# protoboard.net
KiCad netlist of a schematic drawn in EAGLE
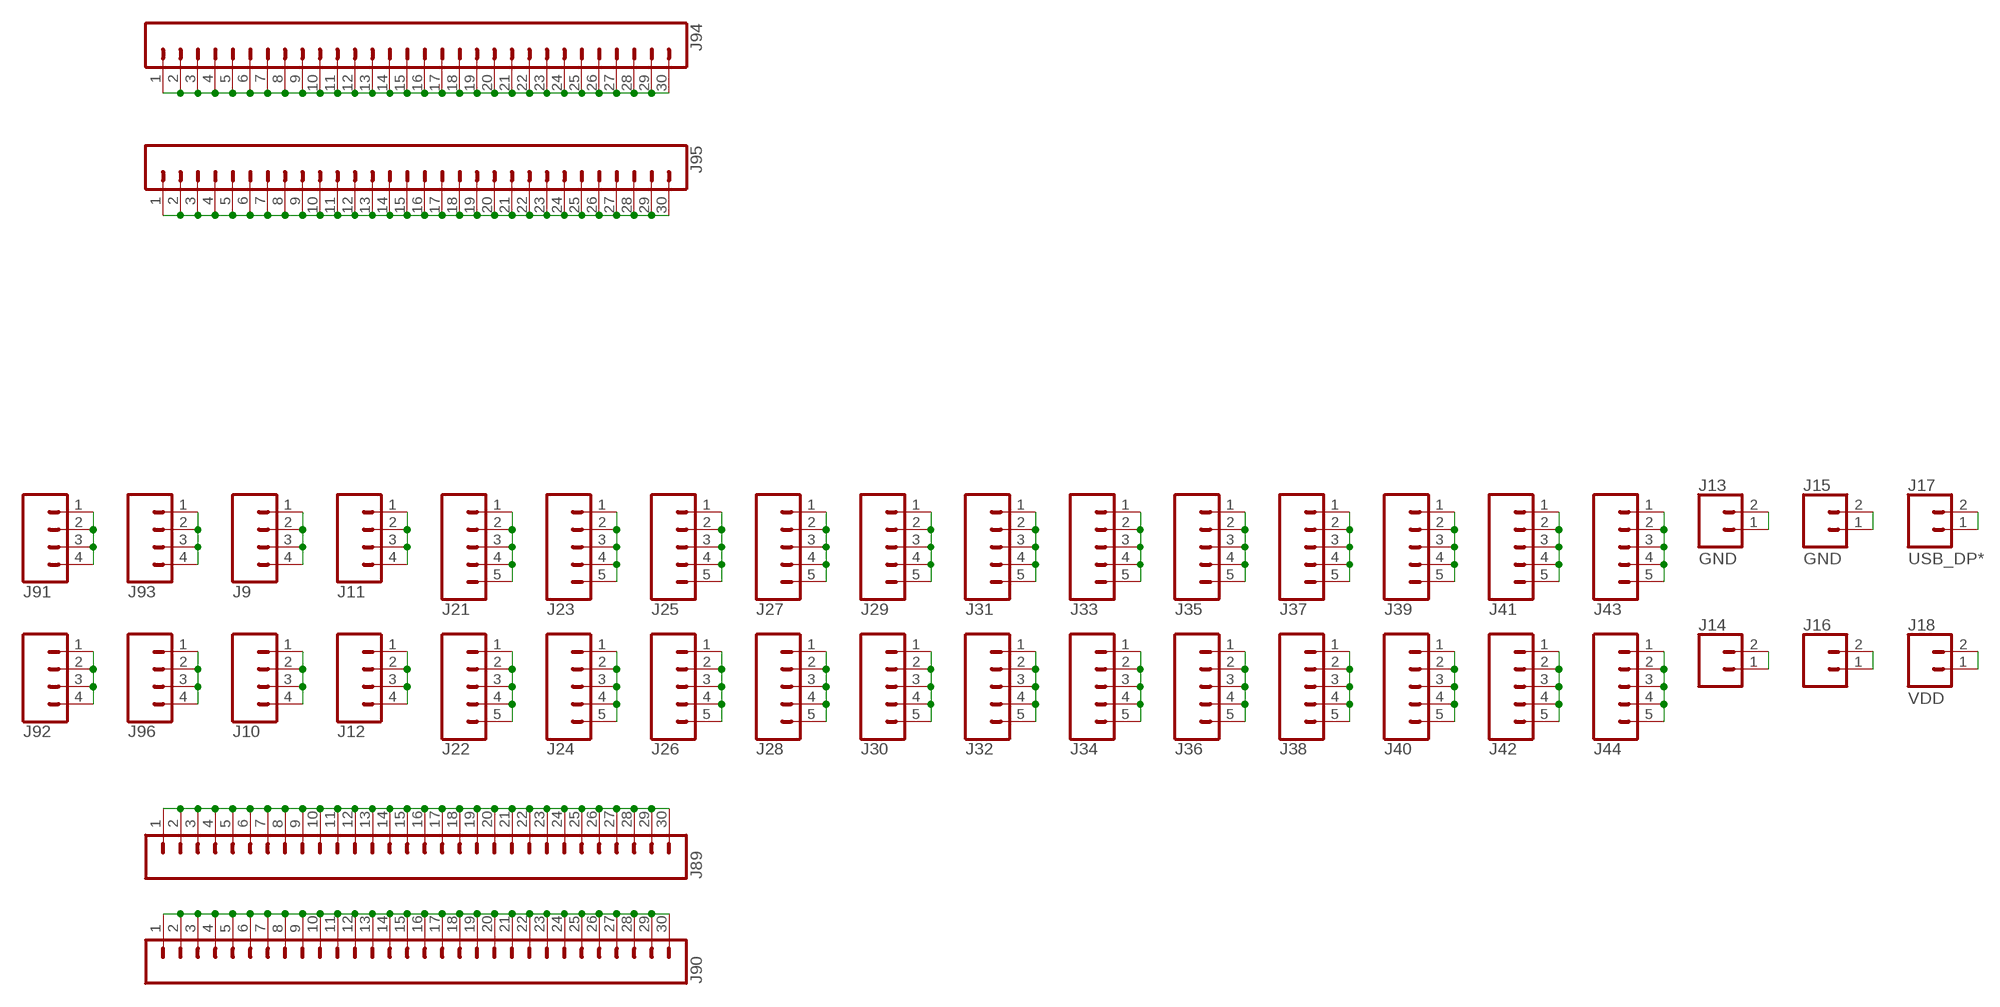
[diagram p0: schematic, sheet 1, part 1 of 2]
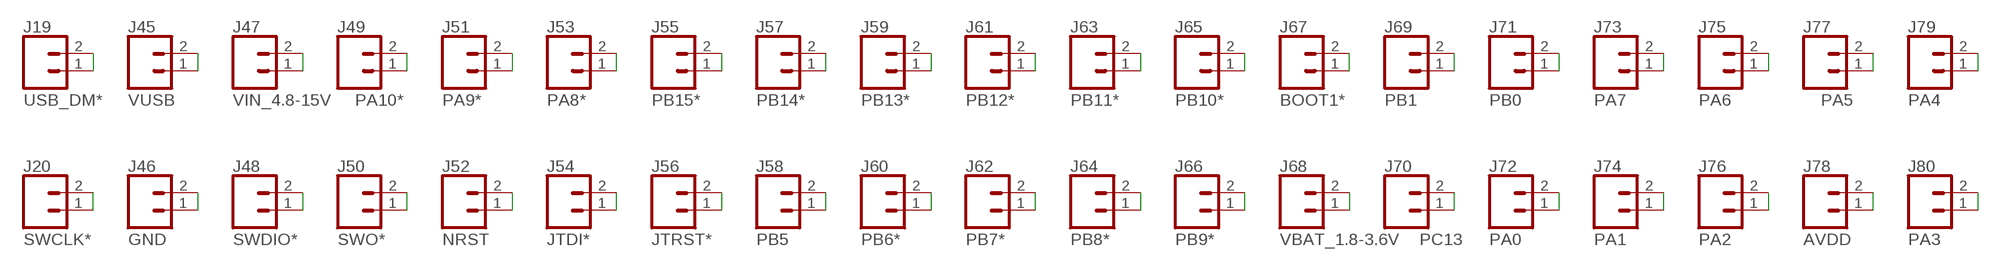
[diagram p1: schematic, sheet 1, part 2 of 2]
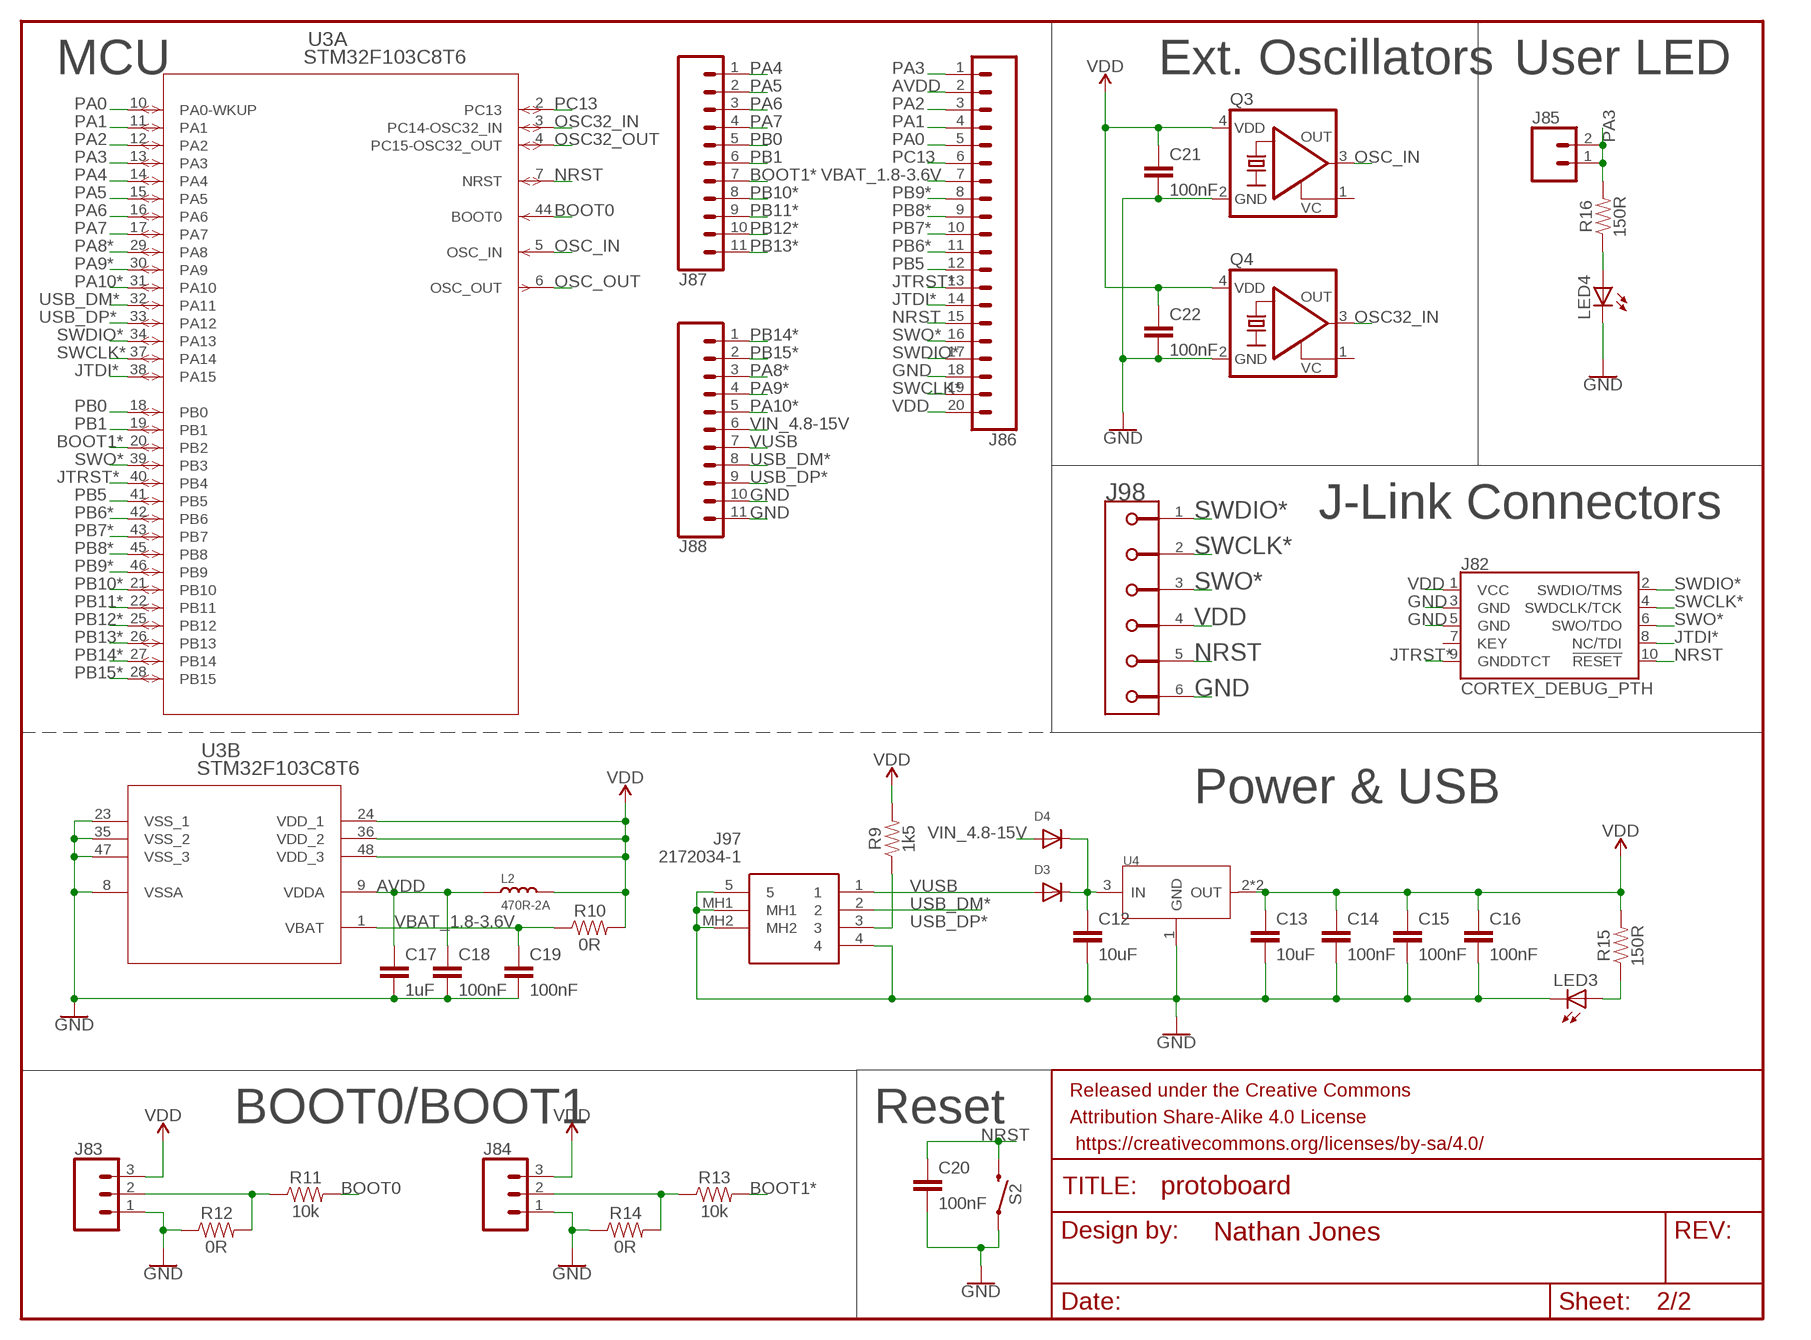
[diagram p2: schematic, sheet 2]

(export (version "E")
  (design (tool "Eeschema 10.0.6"))
  (components
    (comp (ref "C12")
      (value "10uF")
      (footprint "eagle-import:0402-TIGHT")
      (fields (field (name "LCSC_PART") "C15525"))
      (libsource (lib "eagle-import") (part "0.1UF-0402T-16V-10%"))
    )
    (comp (ref "C13")
      (value "10uF")
      (footprint "eagle-import:0402-TIGHT")
      (fields (field (name "LCSC_PART") "C15525"))
      (libsource (lib "eagle-import") (part "0.1UF-0402T-16V-10%"))
    )
    (comp (ref "C14")
      (value "100nF")
      (footprint "eagle-import:0402-TIGHT")
      (fields (field (name "LCSC_PART") "C1525"))
      (libsource (lib "eagle-import") (part "0.1UF-0402T-16V-10%"))
    )
    (comp (ref "C15")
      (value "100nF")
      (footprint "eagle-import:0402-TIGHT")
      (fields (field (name "LCSC_PART") "C1525"))
      (libsource (lib "eagle-import") (part "0.1UF-0402T-16V-10%"))
    )
    (comp (ref "C16")
      (value "100nF")
      (footprint "eagle-import:0402-TIGHT")
      (fields (field (name "LCSC_PART") "C1525"))
      (libsource (lib "eagle-import") (part "0.1UF-0402T-16V-10%"))
    )
    (comp (ref "C17")
      (value "1uF")
      (footprint "eagle-import:0402-TIGHT")
      (fields (field (name "LCSC_PART") "C52923"))
      (libsource (lib "eagle-import") (part "0.1UF-0402T-16V-10%"))
    )
    (comp (ref "C18")
      (value "100nF")
      (footprint "eagle-import:0402-TIGHT")
      (fields (field (name "LCSC_PART") "C1525"))
      (libsource (lib "eagle-import") (part "0.1UF-0402T-16V-10%"))
    )
    (comp (ref "C19")
      (value "100nF")
      (footprint "eagle-import:0402-TIGHT")
      (fields (field (name "LCSC_PART") "C1525"))
      (libsource (lib "eagle-import") (part "0.1UF-0402T-16V-10%"))
    )
    (comp (ref "C20")
      (value "100nF")
      (footprint "eagle-import:0402-TIGHT")
      (fields (field (name "LCSC_PART") "C1525"))
      (libsource (lib "eagle-import") (part "0.1UF-0402T-16V-10%"))
    )
    (comp (ref "C21")
      (value "100nF")
      (footprint "eagle-import:0402-TIGHT")
      (fields (field (name "LCSC_PART") "C1525"))
      (libsource (lib "eagle-import") (part "0.1UF-0402T-16V-10%"))
    )
    (comp (ref "C22")
      (value "100nF")
      (footprint "eagle-import:0402-TIGHT")
      (fields (field (name "LCSC_PART") "C1525"))
      (libsource (lib "eagle-import") (part "0.1UF-0402T-16V-10%"))
    )
    (comp (ref "D3")
      (value "DIODESOD-123")
      (footprint "eagle-import:SOD-123")
      (fields (field (name "LCSC_PART") "C8598"))
      (libsource (lib "eagle-import") (part "DIODESOD-123"))
    )
    (comp (ref "D4")
      (value "DIODESOD-123")
      (footprint "eagle-import:SOD-123")
      (fields (field (name "LCSC_PART") "C8598"))
      (libsource (lib "eagle-import") (part "DIODESOD-123"))
    )
    (comp (ref "FRAME1")
      (value "FRAME-LETTERNO_PACKAGE")
      (footprint "eagle-import:DUMMY")
      (fields (field (name "DESIGNER") "Nathan Jones") (field (name "DESIGNER_1") "Nathan Jones"))
      (libsource (lib "eagle-import") (part "FRAME-LETTERNO_PACKAGE"))
    )
    (comp (ref "J82")
      (value "CORTEX_DEBUG_PTH")
      (footprint "eagle-import:2X5-PTH-1.27MM")
      (libsource (lib "eagle-import") (part "CORTEX_DEBUG_PTH"))
    )
    (comp (ref "J83")
      (value "CONN_031X03_NO_SILK")
      (footprint "eagle-import:1X03_NO_SILK")
      (libsource (lib "eagle-import") (part "CONN_031X03_NO_SILK"))
    )
    (comp (ref "J84")
      (value "CONN_031X03_NO_SILK")
      (footprint "eagle-import:1X03_NO_SILK")
      (libsource (lib "eagle-import") (part "CONN_031X03_NO_SILK"))
    )
    (comp (ref "J85")
      (value "CONN_021X02_NO_SILK")
      (footprint "eagle-import:1X02_NO_SILK")
      (libsource (lib "eagle-import") (part "CONN_021X02_NO_SILK"))
    )
    (comp (ref "J86")
      (value "CONN_20NOSILK")
      (footprint "eagle-import:1X20_NOSILK")
      (libsource (lib "eagle-import") (part "CONN_20NOSILK"))
    )
    (comp (ref "J87")
      (value "CONN_111X11_NO_SILK")
      (footprint "eagle-import:1X11_NO_SILK")
      (libsource (lib "eagle-import") (part "CONN_111X11_NO_SILK"))
    )
    (comp (ref "J88")
      (value "CONN_111X11_NO_SILK")
      (footprint "eagle-import:1X11_NO_SILK")
      (libsource (lib "eagle-import") (part "CONN_111X11_NO_SILK"))
    )
    (comp (ref "J97")
      (value "2172034-1")
      (footprint "eagle-import:21720341")
      (fields (field (name "MOUSER_PART_NUMBER") "571-2172034-1"))
      (libsource (lib "eagle-import") (part "2172034-1"))
    )
    (comp (ref "J98")
      (value "AVX_6-PIN_009159006061916_33MIL-GAP")
      (footprint "eagle-import:AVX_6-PIN_009159006061916_33MIL-GAP")
      (libsource (lib "eagle-import") (part "AVX_6-PIN_009159006061916_33MIL-GAP"))
    )
    (comp (ref "L2")
      (value "470R-2A")
      (footprint "eagle-import:L0805")
      (fields (field (name "MPN") "WLB2012-471T20") (field (name "LCSC_PART") "C1015"))
      (libsource (lib "eagle-import") (part "SMD-FERRITE-BEAD-470R-2A(0805)'0805'"))
    )
    (comp (ref "LED3")
      (value "LEDCHIPLED_0603")
      (footprint "eagle-import:CHIPLED_0603")
      (fields (field (name "LCSC_PART") "C72041"))
      (libsource (lib "eagle-import") (part "LEDCHIPLED_0603"))
    )
    (comp (ref "LED4")
      (value "LEDCHIPLED_0603")
      (footprint "eagle-import:CHIPLED_0603")
      (fields (field (name "LCSC_PART") "C72038"))
      (libsource (lib "eagle-import") (part "LEDCHIPLED_0603"))
    )
    (comp (ref "Q3")
      (value "KXO-VCXO-CMOS_4")
      (footprint "eagle-import:3.2X2.5_KXO-84-TCXO")
      (fields (field (name "LCSC_PART") "C39097"))
      (libsource (lib "eagle-import") (part "KXO-VCXO-CMOS_4"))
    )
    (comp (ref "Q4")
      (value "KXO-VCXO-CMOS_4")
      (footprint "eagle-import:3.2X2.5_KXO-84-TCXO")
      (fields (field (name "LCSC_PART") "C387415"))
      (libsource (lib "eagle-import") (part "KXO-VCXO-CMOS_4"))
    )
    (comp (ref "R9")
      (value "1k5")
      (footprint "eagle-import:0402")
      (fields (field (name "LCSC_PART") "C25867"))
      (libsource (lib "eagle-import") (part "RESISTOR0402"))
    )
    (comp (ref "R10")
      (value "0R")
      (footprint "eagle-import:0402")
      (fields (field (name "LCSC_PART") "C17168"))
      (libsource (lib "eagle-import") (part "RESISTOR0402"))
    )
    (comp (ref "R11")
      (value "10k")
      (footprint "eagle-import:0402")
      (fields (field (name "LCSC_PART") "C25744"))
      (libsource (lib "eagle-import") (part "RESISTOR0402"))
    )
    (comp (ref "R12")
      (value "0R")
      (footprint "eagle-import:0402")
      (fields (field (name "LCSC_PART") "C17168"))
      (libsource (lib "eagle-import") (part "RESISTOR0402"))
    )
    (comp (ref "R13")
      (value "10k")
      (footprint "eagle-import:0402")
      (fields (field (name "LCSC_PART") "C25744"))
      (libsource (lib "eagle-import") (part "RESISTOR0402"))
    )
    (comp (ref "R14")
      (value "0R")
      (footprint "eagle-import:0402")
      (fields (field (name "LCSC_PART") "C17168"))
      (libsource (lib "eagle-import") (part "RESISTOR0402"))
    )
    (comp (ref "R15")
      (value "150R")
      (footprint "eagle-import:0402")
      (fields (field (name "LCSC_PART") "C25082"))
      (libsource (lib "eagle-import") (part "RESISTOR0402"))
    )
    (comp (ref "R16")
      (value "150R")
      (footprint "eagle-import:0402")
      (fields (field (name "LCSC_PART") "C25082"))
      (libsource (lib "eagle-import") (part "RESISTOR0402"))
    )
    (comp (ref "S2")
      (value "MOMENTARY-SWITCH-SPST-SMD-5.2-REDUNDANT")
      (footprint "eagle-import:TACTILE_SWITCH_SMD_5.2MM")
      (fields (field (name "LCSC_PART") "C318884"))
      (libsource (lib "eagle-import") (part "MOMENTARY-SWITCH-SPST-SMD-5.2-REDUNDANT"))
    )
    (comp (ref "U3")
      (value "STM32F103C8T6")
      (footprint "eagle-import:LQFP48-7X7MM")
      (fields
        (field (name "LCSC_PART") "C94046")
        (field (name "COPYRIGHT") "Copyright (C) 2018 Accelerated Designs. All rights reserved")
      )
      (libsource (lib "eagle-import") (part "STM32F103C8T6"))
    )
    (comp (ref "U4")
      (value "CJT1117-3.3-SOT223")
      (footprint "eagle-import:SOT-223")
      (fields (field (name "MPN") "CJT1117-3.3") (field (name "LCSC_PART") "C6186"))
      (libsource (lib "eagle-import") (part "PMIC-CJT1117-3.3(SOT223)"))
    )
    (comp (ref "J9")
      (value "CONN_041X04_NO_SILK")
      (footprint "eagle-import:1X04_NO_SILK")
      (libsource (lib "eagle-import") (part "CONN_041X04_NO_SILK"))
    )
    (comp (ref "J10")
      (value "CONN_041X04_NO_SILK")
      (footprint "eagle-import:1X04_NO_SILK")
      (libsource (lib "eagle-import") (part "CONN_041X04_NO_SILK"))
    )
    (comp (ref "J11")
      (value "CONN_041X04_NO_SILK")
      (footprint "eagle-import:1X04_NO_SILK")
      (libsource (lib "eagle-import") (part "CONN_041X04_NO_SILK"))
    )
    (comp (ref "J12")
      (value "CONN_041X04_NO_SILK")
      (footprint "eagle-import:1X04_NO_SILK")
      (libsource (lib "eagle-import") (part "CONN_041X04_NO_SILK"))
    )
    (comp (ref "J13")
      (value "CONN_021X02_NO_SILK")
      (footprint "eagle-import:1X02_NO_SILK")
      (libsource (lib "eagle-import") (part "CONN_021X02_NO_SILK"))
    )
    (comp (ref "J14")
      (value "CONN_021X02_NO_SILK")
      (footprint "eagle-import:1X02_NO_SILK")
      (libsource (lib "eagle-import") (part "CONN_021X02_NO_SILK"))
    )
    (comp (ref "J15")
      (value "CONN_021X02_NO_SILK")
      (footprint "eagle-import:1X02_NO_SILK")
      (libsource (lib "eagle-import") (part "CONN_021X02_NO_SILK"))
    )
    (comp (ref "J16")
      (value "CONN_021X02_NO_SILK")
      (footprint "eagle-import:1X02_NO_SILK")
      (libsource (lib "eagle-import") (part "CONN_021X02_NO_SILK"))
    )
    (comp (ref "J17")
      (value "CONN_021X02_NO_SILK")
      (footprint "eagle-import:1X02_NO_SILK")
      (libsource (lib "eagle-import") (part "CONN_021X02_NO_SILK"))
    )
    (comp (ref "J18")
      (value "CONN_021X02_NO_SILK")
      (footprint "eagle-import:1X02_NO_SILK")
      (libsource (lib "eagle-import") (part "CONN_021X02_NO_SILK"))
    )
    (comp (ref "J19")
      (value "CONN_021X02_NO_SILK")
      (footprint "eagle-import:1X02_NO_SILK")
      (libsource (lib "eagle-import") (part "CONN_021X02_NO_SILK"))
    )
    (comp (ref "J20")
      (value "CONN_021X02_NO_SILK")
      (footprint "eagle-import:1X02_NO_SILK")
      (libsource (lib "eagle-import") (part "CONN_021X02_NO_SILK"))
    )
    (comp (ref "J21")
      (value "CONN_05NO_SILK")
      (footprint "eagle-import:1X05_NO_SILK")
      (libsource (lib "eagle-import") (part "CONN_05NO_SILK"))
    )
    (comp (ref "J22")
      (value "CONN_05NO_SILK")
      (footprint "eagle-import:1X05_NO_SILK")
      (libsource (lib "eagle-import") (part "CONN_05NO_SILK"))
    )
    (comp (ref "J23")
      (value "CONN_05NO_SILK")
      (footprint "eagle-import:1X05_NO_SILK")
      (libsource (lib "eagle-import") (part "CONN_05NO_SILK"))
    )
    (comp (ref "J24")
      (value "CONN_05NO_SILK")
      (footprint "eagle-import:1X05_NO_SILK")
      (libsource (lib "eagle-import") (part "CONN_05NO_SILK"))
    )
    (comp (ref "J25")
      (value "CONN_05NO_SILK")
      (footprint "eagle-import:1X05_NO_SILK")
      (libsource (lib "eagle-import") (part "CONN_05NO_SILK"))
    )
    (comp (ref "J26")
      (value "CONN_05NO_SILK")
      (footprint "eagle-import:1X05_NO_SILK")
      (libsource (lib "eagle-import") (part "CONN_05NO_SILK"))
    )
    (comp (ref "J27")
      (value "CONN_05NO_SILK")
      (footprint "eagle-import:1X05_NO_SILK")
      (libsource (lib "eagle-import") (part "CONN_05NO_SILK"))
    )
    (comp (ref "J28")
      (value "CONN_05NO_SILK")
      (footprint "eagle-import:1X05_NO_SILK")
      (libsource (lib "eagle-import") (part "CONN_05NO_SILK"))
    )
    (comp (ref "J29")
      (value "CONN_05NO_SILK")
      (footprint "eagle-import:1X05_NO_SILK")
      (libsource (lib "eagle-import") (part "CONN_05NO_SILK"))
    )
    (comp (ref "J30")
      (value "CONN_05NO_SILK")
      (footprint "eagle-import:1X05_NO_SILK")
      (libsource (lib "eagle-import") (part "CONN_05NO_SILK"))
    )
    (comp (ref "J31")
      (value "CONN_05NO_SILK")
      (footprint "eagle-import:1X05_NO_SILK")
      (libsource (lib "eagle-import") (part "CONN_05NO_SILK"))
    )
    (comp (ref "J32")
      (value "CONN_05NO_SILK")
      (footprint "eagle-import:1X05_NO_SILK")
      (libsource (lib "eagle-import") (part "CONN_05NO_SILK"))
    )
    (comp (ref "J33")
      (value "CONN_05NO_SILK")
      (footprint "eagle-import:1X05_NO_SILK")
      (libsource (lib "eagle-import") (part "CONN_05NO_SILK"))
    )
    (comp (ref "J34")
      (value "CONN_05NO_SILK")
      (footprint "eagle-import:1X05_NO_SILK")
      (libsource (lib "eagle-import") (part "CONN_05NO_SILK"))
    )
    (comp (ref "J35")
      (value "CONN_05NO_SILK")
      (footprint "eagle-import:1X05_NO_SILK")
      (libsource (lib "eagle-import") (part "CONN_05NO_SILK"))
    )
    (comp (ref "J36")
      (value "CONN_05NO_SILK")
      (footprint "eagle-import:1X05_NO_SILK")
      (libsource (lib "eagle-import") (part "CONN_05NO_SILK"))
    )
    (comp (ref "J37")
      (value "CONN_05NO_SILK")
      (footprint "eagle-import:1X05_NO_SILK")
      (libsource (lib "eagle-import") (part "CONN_05NO_SILK"))
    )
    (comp (ref "J38")
      (value "CONN_05NO_SILK")
      (footprint "eagle-import:1X05_NO_SILK")
      (libsource (lib "eagle-import") (part "CONN_05NO_SILK"))
    )
    (comp (ref "J39")
      (value "CONN_05NO_SILK")
      (footprint "eagle-import:1X05_NO_SILK")
      (libsource (lib "eagle-import") (part "CONN_05NO_SILK"))
    )
    (comp (ref "J40")
      (value "CONN_05NO_SILK")
      (footprint "eagle-import:1X05_NO_SILK")
      (libsource (lib "eagle-import") (part "CONN_05NO_SILK"))
    )
    (comp (ref "J41")
      (value "CONN_05NO_SILK")
      (footprint "eagle-import:1X05_NO_SILK")
      (libsource (lib "eagle-import") (part "CONN_05NO_SILK"))
    )
    (comp (ref "J42")
      (value "CONN_05NO_SILK")
      (footprint "eagle-import:1X05_NO_SILK")
      (libsource (lib "eagle-import") (part "CONN_05NO_SILK"))
    )
    (comp (ref "J43")
      (value "CONN_05NO_SILK")
      (footprint "eagle-import:1X05_NO_SILK")
      (libsource (lib "eagle-import") (part "CONN_05NO_SILK"))
    )
    (comp (ref "J44")
      (value "CONN_05NO_SILK")
      (footprint "eagle-import:1X05_NO_SILK")
      (libsource (lib "eagle-import") (part "CONN_05NO_SILK"))
    )
    (comp (ref "J45")
      (value "CONN_021X02_NO_SILK")
      (footprint "eagle-import:1X02_NO_SILK")
      (libsource (lib "eagle-import") (part "CONN_021X02_NO_SILK"))
    )
    (comp (ref "J46")
      (value "CONN_021X02_NO_SILK")
      (footprint "eagle-import:1X02_NO_SILK")
      (libsource (lib "eagle-import") (part "CONN_021X02_NO_SILK"))
    )
    (comp (ref "J47")
      (value "CONN_021X02_NO_SILK")
      (footprint "eagle-import:1X02_NO_SILK")
      (libsource (lib "eagle-import") (part "CONN_021X02_NO_SILK"))
    )
    (comp (ref "J48")
      (value "CONN_021X02_NO_SILK")
      (footprint "eagle-import:1X02_NO_SILK")
      (libsource (lib "eagle-import") (part "CONN_021X02_NO_SILK"))
    )
    (comp (ref "J49")
      (value "CONN_021X02_NO_SILK")
      (footprint "eagle-import:1X02_NO_SILK")
      (libsource (lib "eagle-import") (part "CONN_021X02_NO_SILK"))
    )
    (comp (ref "J50")
      (value "CONN_021X02_NO_SILK")
      (footprint "eagle-import:1X02_NO_SILK")
      (libsource (lib "eagle-import") (part "CONN_021X02_NO_SILK"))
    )
    (comp (ref "J51")
      (value "CONN_021X02_NO_SILK")
      (footprint "eagle-import:1X02_NO_SILK")
      (libsource (lib "eagle-import") (part "CONN_021X02_NO_SILK"))
    )
    (comp (ref "J52")
      (value "CONN_021X02_NO_SILK")
      (footprint "eagle-import:1X02_NO_SILK")
      (libsource (lib "eagle-import") (part "CONN_021X02_NO_SILK"))
    )
    (comp (ref "J53")
      (value "CONN_021X02_NO_SILK")
      (footprint "eagle-import:1X02_NO_SILK")
      (libsource (lib "eagle-import") (part "CONN_021X02_NO_SILK"))
    )
    (comp (ref "J54")
      (value "CONN_021X02_NO_SILK")
      (footprint "eagle-import:1X02_NO_SILK")
      (libsource (lib "eagle-import") (part "CONN_021X02_NO_SILK"))
    )
    (comp (ref "J55")
      (value "CONN_021X02_NO_SILK")
      (footprint "eagle-import:1X02_NO_SILK")
      (libsource (lib "eagle-import") (part "CONN_021X02_NO_SILK"))
    )
    (comp (ref "J56")
      (value "CONN_021X02_NO_SILK")
      (footprint "eagle-import:1X02_NO_SILK")
      (libsource (lib "eagle-import") (part "CONN_021X02_NO_SILK"))
    )
    (comp (ref "J57")
      (value "CONN_021X02_NO_SILK")
      (footprint "eagle-import:1X02_NO_SILK")
      (libsource (lib "eagle-import") (part "CONN_021X02_NO_SILK"))
    )
    (comp (ref "J58")
      (value "CONN_021X02_NO_SILK")
      (footprint "eagle-import:1X02_NO_SILK")
      (libsource (lib "eagle-import") (part "CONN_021X02_NO_SILK"))
    )
    (comp (ref "J59")
      (value "CONN_021X02_NO_SILK")
      (footprint "eagle-import:1X02_NO_SILK")
      (libsource (lib "eagle-import") (part "CONN_021X02_NO_SILK"))
    )
    (comp (ref "J60")
      (value "CONN_021X02_NO_SILK")
      (footprint "eagle-import:1X02_NO_SILK")
      (libsource (lib "eagle-import") (part "CONN_021X02_NO_SILK"))
    )
    (comp (ref "J61")
      (value "CONN_021X02_NO_SILK")
      (footprint "eagle-import:1X02_NO_SILK")
      (libsource (lib "eagle-import") (part "CONN_021X02_NO_SILK"))
    )
    (comp (ref "J62")
      (value "CONN_021X02_NO_SILK")
      (footprint "eagle-import:1X02_NO_SILK")
      (libsource (lib "eagle-import") (part "CONN_021X02_NO_SILK"))
    )
    (comp (ref "J63")
      (value "CONN_021X02_NO_SILK")
      (footprint "eagle-import:1X02_NO_SILK")
      (libsource (lib "eagle-import") (part "CONN_021X02_NO_SILK"))
    )
    (comp (ref "J64")
      (value "CONN_021X02_NO_SILK")
      (footprint "eagle-import:1X02_NO_SILK")
      (libsource (lib "eagle-import") (part "CONN_021X02_NO_SILK"))
    )
    (comp (ref "J65")
      (value "CONN_021X02_NO_SILK")
      (footprint "eagle-import:1X02_NO_SILK")
      (libsource (lib "eagle-import") (part "CONN_021X02_NO_SILK"))
    )
    (comp (ref "J66")
      (value "CONN_021X02_NO_SILK")
      (footprint "eagle-import:1X02_NO_SILK")
      (libsource (lib "eagle-import") (part "CONN_021X02_NO_SILK"))
    )
    (comp (ref "J67")
      (value "CONN_021X02_NO_SILK")
      (footprint "eagle-import:1X02_NO_SILK")
      (libsource (lib "eagle-import") (part "CONN_021X02_NO_SILK"))
    )
    (comp (ref "J68")
      (value "CONN_021X02_NO_SILK")
      (footprint "eagle-import:1X02_NO_SILK")
      (libsource (lib "eagle-import") (part "CONN_021X02_NO_SILK"))
    )
    (comp (ref "J69")
      (value "CONN_021X02_NO_SILK")
      (footprint "eagle-import:1X02_NO_SILK")
      (libsource (lib "eagle-import") (part "CONN_021X02_NO_SILK"))
    )
    (comp (ref "J70")
      (value "CONN_021X02_NO_SILK")
      (footprint "eagle-import:1X02_NO_SILK")
      (libsource (lib "eagle-import") (part "CONN_021X02_NO_SILK"))
    )
    (comp (ref "J71")
      (value "CONN_021X02_NO_SILK")
      (footprint "eagle-import:1X02_NO_SILK")
      (libsource (lib "eagle-import") (part "CONN_021X02_NO_SILK"))
    )
    (comp (ref "J72")
      (value "CONN_021X02_NO_SILK")
      (footprint "eagle-import:1X02_NO_SILK")
      (libsource (lib "eagle-import") (part "CONN_021X02_NO_SILK"))
    )
    (comp (ref "J73")
      (value "CONN_021X02_NO_SILK")
      (footprint "eagle-import:1X02_NO_SILK")
      (libsource (lib "eagle-import") (part "CONN_021X02_NO_SILK"))
    )
    (comp (ref "J74")
      (value "CONN_021X02_NO_SILK")
      (footprint "eagle-import:1X02_NO_SILK")
      (libsource (lib "eagle-import") (part "CONN_021X02_NO_SILK"))
    )
    (comp (ref "J75")
      (value "CONN_021X02_NO_SILK")
      (footprint "eagle-import:1X02_NO_SILK")
      (libsource (lib "eagle-import") (part "CONN_021X02_NO_SILK"))
    )
    (comp (ref "J76")
      (value "CONN_021X02_NO_SILK")
      (footprint "eagle-import:1X02_NO_SILK")
      (libsource (lib "eagle-import") (part "CONN_021X02_NO_SILK"))
    )
    (comp (ref "J77")
      (value "CONN_021X02_NO_SILK")
      (footprint "eagle-import:1X02_NO_SILK")
      (libsource (lib "eagle-import") (part "CONN_021X02_NO_SILK"))
    )
    (comp (ref "J78")
      (value "CONN_021X02_NO_SILK")
      (footprint "eagle-import:1X02_NO_SILK")
      (libsource (lib "eagle-import") (part "CONN_021X02_NO_SILK"))
    )
    (comp (ref "J79")
      (value "CONN_021X02_NO_SILK")
      (footprint "eagle-import:1X02_NO_SILK")
      (libsource (lib "eagle-import") (part "CONN_021X02_NO_SILK"))
    )
    (comp (ref "J80")
      (value "CONN_021X02_NO_SILK")
      (footprint "eagle-import:1X02_NO_SILK")
      (libsource (lib "eagle-import") (part "CONN_021X02_NO_SILK"))
    )
    (comp (ref "J89")
      (value "CONN_30NO_SILK")
      (footprint "eagle-import:1X30_NO_SILK")
      (libsource (lib "eagle-import") (part "CONN_30NO_SILK"))
    )
    (comp (ref "J90")
      (value "CONN_30NO_SILK")
      (footprint "eagle-import:1X30_NO_SILK")
      (libsource (lib "eagle-import") (part "CONN_30NO_SILK"))
    )
    (comp (ref "J91")
      (value "CONN_041X04_NO_SILK")
      (footprint "eagle-import:1X04_NO_SILK")
      (libsource (lib "eagle-import") (part "CONN_041X04_NO_SILK"))
    )
    (comp (ref "J92")
      (value "CONN_041X04_NO_SILK")
      (footprint "eagle-import:1X04_NO_SILK")
      (libsource (lib "eagle-import") (part "CONN_041X04_NO_SILK"))
    )
    (comp (ref "J93")
      (value "CONN_041X04_NO_SILK")
      (footprint "eagle-import:1X04_NO_SILK")
      (libsource (lib "eagle-import") (part "CONN_041X04_NO_SILK"))
    )
    (comp (ref "J94")
      (value "CONN_30NO_SILK")
      (footprint "eagle-import:1X30_NO_SILK")
      (libsource (lib "eagle-import") (part "CONN_30NO_SILK"))
    )
    (comp (ref "J95")
      (value "CONN_30NO_SILK")
      (footprint "eagle-import:1X30_NO_SILK")
      (libsource (lib "eagle-import") (part "CONN_30NO_SILK"))
    )
    (comp (ref "J96")
      (value "CONN_041X04_NO_SILK")
      (footprint "eagle-import:1X04_NO_SILK")
      (libsource (lib "eagle-import") (part "CONN_041X04_NO_SILK"))
    )
  )
  (nets
    (net (code "1") (name "AVDD") (class "Default")
      (node (ref "C17") (pin "1") (pinfunction "1_1") (pintype "passive"))
      (node (ref "C18") (pin "1") (pinfunction "1_1") (pintype "passive"))
      (node (ref "J78") (pin "1") (pinfunction "1_1") (pintype "passive"))
      (node (ref "J78") (pin "2") (pinfunction "2_2") (pintype "passive"))
      (node (ref "J86") (pin "2") (pinfunction "2_2") (pintype "passive"))
      (node (ref "L2") (pin "1") (pinfunction "1_1") (pintype "passive"))
      (node (ref "U3") (pin "9") (pinfunction "VDDA_9") (pintype "power_in"))
    )
    (net (code "2") (name "BOOT0") (class "Default")
      (node (ref "R11") (pin "2") (pinfunction "2_2") (pintype "passive"))
      (node (ref "U3") (pin "44") (pinfunction "BOOT0_44") (pintype "input"))
    )
    (net (code "3") (name "BOOT1*") (class "Default")
      (node (ref "J67") (pin "1") (pinfunction "1_1") (pintype "passive"))
      (node (ref "J67") (pin "2") (pinfunction "2_2") (pintype "passive"))
      (node (ref "J87") (pin "7") (pinfunction "7_7") (pintype "passive"))
      (node (ref "R13") (pin "2") (pinfunction "2_2") (pintype "passive"))
      (node (ref "U3") (pin "20") (pinfunction "PB2_20") (pintype "bidirectional"))
    )
    (net (code "4") (name "GND") (class "Default")
      (node (ref "C12") (pin "2") (pinfunction "2_2") (pintype "passive"))
      (node (ref "C13") (pin "2") (pinfunction "2_2") (pintype "passive"))
      (node (ref "C14") (pin "2") (pinfunction "2_2") (pintype "passive"))
      (node (ref "C15") (pin "2") (pinfunction "2_2") (pintype "passive"))
      (node (ref "C16") (pin "2") (pinfunction "2_2") (pintype "passive"))
      (node (ref "C17") (pin "2") (pinfunction "2_2") (pintype "passive"))
      (node (ref "C18") (pin "2") (pinfunction "2_2") (pintype "passive"))
      (node (ref "C19") (pin "2") (pinfunction "2_2") (pintype "passive"))
      (node (ref "C20") (pin "2") (pinfunction "2_2") (pintype "passive"))
      (node (ref "C21") (pin "2") (pinfunction "2_2") (pintype "passive"))
      (node (ref "C22") (pin "2") (pinfunction "2_2") (pintype "passive"))
      (node (ref "J13") (pin "1") (pinfunction "1_1") (pintype "passive"))
      (node (ref "J13") (pin "2") (pinfunction "2_2") (pintype "passive"))
      (node (ref "J15") (pin "1") (pinfunction "1_1") (pintype "passive"))
      (node (ref "J15") (pin "2") (pinfunction "2_2") (pintype "passive"))
      (node (ref "J46") (pin "1") (pinfunction "1_1") (pintype "passive"))
      (node (ref "J46") (pin "2") (pinfunction "2_2") (pintype "passive"))
      (node (ref "J82") (pin "3") (pinfunction "GND_3") (pintype "bidirectional"))
      (node (ref "J82") (pin "5") (pinfunction "GND_5") (pintype "bidirectional"))
      (node (ref "J83") (pin "1") (pinfunction "1_1") (pintype "passive"))
      (node (ref "J84") (pin "1") (pinfunction "1_1") (pintype "passive"))
      (node (ref "J86") (pin "18") (pinfunction "18_18") (pintype "passive"))
      (node (ref "J88") (pin "10") (pinfunction "10_10") (pintype "passive"))
      (node (ref "J88") (pin "11") (pinfunction "11_11") (pintype "passive"))
      (node (ref "J97") (pin "4") (pinfunction "4_4") (pintype "bidirectional"))
      (node (ref "J97") (pin "5") (pinfunction "5_5") (pintype "bidirectional"))
      (node (ref "J97") (pin "MH1") (pinfunction "MH1_MH1") (pintype "bidirectional"))
      (node (ref "J97") (pin "MH2") (pinfunction "MH2_MH2") (pintype "bidirectional"))
      (node (ref "J98") (pin "6") (pinfunction "6_6") (pintype "bidirectional"))
      (node (ref "LED3") (pin "C") (pinfunction "C_C") (pintype "passive"))
      (node (ref "LED4") (pin "C") (pinfunction "C_C") (pintype "passive"))
      (node (ref "Q3") (pin "2") (pinfunction "GND_2") (pintype "power_in"))
      (node (ref "Q4") (pin "2") (pinfunction "GND_2") (pintype "power_in"))
      (node (ref "R12") (pin "1") (pinfunction "1_1") (pintype "passive"))
      (node (ref "R14") (pin "1") (pinfunction "1_1") (pintype "passive"))
      (node (ref "S2") (pin "1") (pinfunction "1_1") (pintype "passive"))
      (node (ref "S2") (pin "2") (pinfunction "1_2") (pintype "passive"))
      (node (ref "U3") (pin "23") (pinfunction "VSS_1_23") (pintype "power_in"))
      (node (ref "U3") (pin "35") (pinfunction "VSS_2_35") (pintype "power_in"))
      (node (ref "U3") (pin "47") (pinfunction "VSS_3_47") (pintype "power_in"))
      (node (ref "U3") (pin "8") (pinfunction "VSSA_8") (pintype "power_in"))
      (node (ref "U4") (pin "1") (pinfunction "GND_1") (pintype "bidirectional"))
    )
    (net (code "5") (name "JTDI*") (class "Default")
      (node (ref "J54") (pin "1") (pinfunction "1_1") (pintype "passive"))
      (node (ref "J54") (pin "2") (pinfunction "2_2") (pintype "passive"))
      (node (ref "J82") (pin "8") (pinfunction "NC/TDI_8") (pintype "bidirectional"))
      (node (ref "J86") (pin "14") (pinfunction "14_14") (pintype "passive"))
      (node (ref "U3") (pin "38") (pinfunction "PA15_38") (pintype "bidirectional"))
    )
    (net (code "6") (name "JTRST*") (class "Default")
      (node (ref "J56") (pin "1") (pinfunction "1_1") (pintype "passive"))
      (node (ref "J56") (pin "2") (pinfunction "2_2") (pintype "passive"))
      (node (ref "J82") (pin "9") (pinfunction "GNDDTCT_9") (pintype "bidirectional"))
      (node (ref "J86") (pin "13") (pinfunction "13_13") (pintype "passive"))
      (node (ref "U3") (pin "40") (pinfunction "PB4_40") (pintype "bidirectional"))
    )
    (net (code "7") (name "NRST") (class "Default")
      (node (ref "C20") (pin "1") (pinfunction "1_1") (pintype "passive"))
      (node (ref "J52") (pin "1") (pinfunction "1_1") (pintype "passive"))
      (node (ref "J52") (pin "2") (pinfunction "2_2") (pintype "passive"))
      (node (ref "J82") (pin "10") (pinfunction "~{RESET}_10") (pintype "bidirectional"))
      (node (ref "J86") (pin "15") (pinfunction "15_15") (pintype "passive"))
      (node (ref "J98") (pin "5") (pinfunction "5_5") (pintype "bidirectional"))
      (node (ref "S2") (pin "3") (pinfunction "2_3") (pintype "passive"))
      (node (ref "S2") (pin "4") (pinfunction "2_4") (pintype "passive"))
      (node (ref "U3") (pin "7") (pinfunction "NRST_7") (pintype "bidirectional"))
    )
    (net (code "8") (name "Net-(J9-Pad1)") (class "Default")
      (node (ref "J9") (pin "1") (pinfunction "1_1") (pintype "passive"))
      (node (ref "J9") (pin "2") (pinfunction "2_2") (pintype "passive"))
      (node (ref "J9") (pin "3") (pinfunction "3_3") (pintype "passive"))
      (node (ref "J9") (pin "4") (pinfunction "4_4") (pintype "passive"))
    )
    (net (code "9") (name "Net-(J10-Pad1)") (class "Default")
      (node (ref "J10") (pin "1") (pinfunction "1_1") (pintype "passive"))
      (node (ref "J10") (pin "2") (pinfunction "2_2") (pintype "passive"))
      (node (ref "J10") (pin "3") (pinfunction "3_3") (pintype "passive"))
      (node (ref "J10") (pin "4") (pinfunction "4_4") (pintype "passive"))
    )
    (net (code "10") (name "Net-(J11-Pad1)") (class "Default")
      (node (ref "J11") (pin "1") (pinfunction "1_1") (pintype "passive"))
      (node (ref "J11") (pin "2") (pinfunction "2_2") (pintype "passive"))
      (node (ref "J11") (pin "3") (pinfunction "3_3") (pintype "passive"))
      (node (ref "J11") (pin "4") (pinfunction "4_4") (pintype "passive"))
    )
    (net (code "11") (name "Net-(J12-Pad1)") (class "Default")
      (node (ref "J12") (pin "1") (pinfunction "1_1") (pintype "passive"))
      (node (ref "J12") (pin "2") (pinfunction "2_2") (pintype "passive"))
      (node (ref "J12") (pin "3") (pinfunction "3_3") (pintype "passive"))
      (node (ref "J12") (pin "4") (pinfunction "4_4") (pintype "passive"))
    )
    (net (code "12") (name "Net-(J14-Pad1)") (class "Default")
      (node (ref "J14") (pin "1") (pinfunction "1_1") (pintype "passive"))
      (node (ref "J14") (pin "2") (pinfunction "2_2") (pintype "passive"))
    )
    (net (code "13") (name "Net-(J16-Pad1)") (class "Default")
      (node (ref "J16") (pin "1") (pinfunction "1_1") (pintype "passive"))
      (node (ref "J16") (pin "2") (pinfunction "2_2") (pintype "passive"))
    )
    (net (code "14") (name "Net-(J21-Pad1)") (class "Default")
      (node (ref "J21") (pin "1") (pinfunction "1_1") (pintype "passive"))
      (node (ref "J21") (pin "2") (pinfunction "2_2") (pintype "passive"))
      (node (ref "J21") (pin "3") (pinfunction "3_3") (pintype "passive"))
      (node (ref "J21") (pin "4") (pinfunction "4_4") (pintype "passive"))
      (node (ref "J21") (pin "5") (pinfunction "5_5") (pintype "passive"))
    )
    (net (code "15") (name "Net-(J22-Pad1)") (class "Default")
      (node (ref "J22") (pin "1") (pinfunction "1_1") (pintype "passive"))
      (node (ref "J22") (pin "2") (pinfunction "2_2") (pintype "passive"))
      (node (ref "J22") (pin "3") (pinfunction "3_3") (pintype "passive"))
      (node (ref "J22") (pin "4") (pinfunction "4_4") (pintype "passive"))
      (node (ref "J22") (pin "5") (pinfunction "5_5") (pintype "passive"))
    )
    (net (code "16") (name "Net-(J23-Pad1)") (class "Default")
      (node (ref "J23") (pin "1") (pinfunction "1_1") (pintype "passive"))
      (node (ref "J23") (pin "2") (pinfunction "2_2") (pintype "passive"))
      (node (ref "J23") (pin "3") (pinfunction "3_3") (pintype "passive"))
      (node (ref "J23") (pin "4") (pinfunction "4_4") (pintype "passive"))
      (node (ref "J23") (pin "5") (pinfunction "5_5") (pintype "passive"))
    )
    (net (code "17") (name "Net-(J24-Pad1)") (class "Default")
      (node (ref "J24") (pin "1") (pinfunction "1_1") (pintype "passive"))
      (node (ref "J24") (pin "2") (pinfunction "2_2") (pintype "passive"))
      (node (ref "J24") (pin "3") (pinfunction "3_3") (pintype "passive"))
      (node (ref "J24") (pin "4") (pinfunction "4_4") (pintype "passive"))
      (node (ref "J24") (pin "5") (pinfunction "5_5") (pintype "passive"))
    )
    (net (code "18") (name "Net-(J25-Pad1)") (class "Default")
      (node (ref "J25") (pin "1") (pinfunction "1_1") (pintype "passive"))
      (node (ref "J25") (pin "2") (pinfunction "2_2") (pintype "passive"))
      (node (ref "J25") (pin "3") (pinfunction "3_3") (pintype "passive"))
      (node (ref "J25") (pin "4") (pinfunction "4_4") (pintype "passive"))
      (node (ref "J25") (pin "5") (pinfunction "5_5") (pintype "passive"))
    )
    (net (code "19") (name "Net-(J26-Pad1)") (class "Default")
      (node (ref "J26") (pin "1") (pinfunction "1_1") (pintype "passive"))
      (node (ref "J26") (pin "2") (pinfunction "2_2") (pintype "passive"))
      (node (ref "J26") (pin "3") (pinfunction "3_3") (pintype "passive"))
      (node (ref "J26") (pin "4") (pinfunction "4_4") (pintype "passive"))
      (node (ref "J26") (pin "5") (pinfunction "5_5") (pintype "passive"))
    )
    (net (code "20") (name "Net-(J27-Pad1)") (class "Default")
      (node (ref "J27") (pin "1") (pinfunction "1_1") (pintype "passive"))
      (node (ref "J27") (pin "2") (pinfunction "2_2") (pintype "passive"))
      (node (ref "J27") (pin "3") (pinfunction "3_3") (pintype "passive"))
      (node (ref "J27") (pin "4") (pinfunction "4_4") (pintype "passive"))
      (node (ref "J27") (pin "5") (pinfunction "5_5") (pintype "passive"))
    )
    (net (code "21") (name "Net-(J28-Pad1)") (class "Default")
      (node (ref "J28") (pin "1") (pinfunction "1_1") (pintype "passive"))
      (node (ref "J28") (pin "2") (pinfunction "2_2") (pintype "passive"))
      (node (ref "J28") (pin "3") (pinfunction "3_3") (pintype "passive"))
      (node (ref "J28") (pin "4") (pinfunction "4_4") (pintype "passive"))
      (node (ref "J28") (pin "5") (pinfunction "5_5") (pintype "passive"))
    )
    (net (code "22") (name "Net-(J29-Pad1)") (class "Default")
      (node (ref "J29") (pin "1") (pinfunction "1_1") (pintype "passive"))
      (node (ref "J29") (pin "2") (pinfunction "2_2") (pintype "passive"))
      (node (ref "J29") (pin "3") (pinfunction "3_3") (pintype "passive"))
      (node (ref "J29") (pin "4") (pinfunction "4_4") (pintype "passive"))
      (node (ref "J29") (pin "5") (pinfunction "5_5") (pintype "passive"))
    )
    (net (code "23") (name "Net-(J30-Pad1)") (class "Default")
      (node (ref "J30") (pin "1") (pinfunction "1_1") (pintype "passive"))
      (node (ref "J30") (pin "2") (pinfunction "2_2") (pintype "passive"))
      (node (ref "J30") (pin "3") (pinfunction "3_3") (pintype "passive"))
      (node (ref "J30") (pin "4") (pinfunction "4_4") (pintype "passive"))
      (node (ref "J30") (pin "5") (pinfunction "5_5") (pintype "passive"))
    )
    (net (code "24") (name "Net-(J31-Pad1)") (class "Default")
      (node (ref "J31") (pin "1") (pinfunction "1_1") (pintype "passive"))
      (node (ref "J31") (pin "2") (pinfunction "2_2") (pintype "passive"))
      (node (ref "J31") (pin "3") (pinfunction "3_3") (pintype "passive"))
      (node (ref "J31") (pin "4") (pinfunction "4_4") (pintype "passive"))
      (node (ref "J31") (pin "5") (pinfunction "5_5") (pintype "passive"))
    )
    (net (code "25") (name "Net-(J32-Pad1)") (class "Default")
      (node (ref "J32") (pin "1") (pinfunction "1_1") (pintype "passive"))
      (node (ref "J32") (pin "2") (pinfunction "2_2") (pintype "passive"))
      (node (ref "J32") (pin "3") (pinfunction "3_3") (pintype "passive"))
      (node (ref "J32") (pin "4") (pinfunction "4_4") (pintype "passive"))
      (node (ref "J32") (pin "5") (pinfunction "5_5") (pintype "passive"))
    )
    (net (code "26") (name "Net-(J33-Pad1)") (class "Default")
      (node (ref "J33") (pin "1") (pinfunction "1_1") (pintype "passive"))
      (node (ref "J33") (pin "2") (pinfunction "2_2") (pintype "passive"))
      (node (ref "J33") (pin "3") (pinfunction "3_3") (pintype "passive"))
      (node (ref "J33") (pin "4") (pinfunction "4_4") (pintype "passive"))
      (node (ref "J33") (pin "5") (pinfunction "5_5") (pintype "passive"))
    )
    (net (code "27") (name "Net-(J34-Pad1)") (class "Default")
      (node (ref "J34") (pin "1") (pinfunction "1_1") (pintype "passive"))
      (node (ref "J34") (pin "2") (pinfunction "2_2") (pintype "passive"))
      (node (ref "J34") (pin "3") (pinfunction "3_3") (pintype "passive"))
      (node (ref "J34") (pin "4") (pinfunction "4_4") (pintype "passive"))
      (node (ref "J34") (pin "5") (pinfunction "5_5") (pintype "passive"))
    )
    (net (code "28") (name "Net-(J35-Pad1)") (class "Default")
      (node (ref "J35") (pin "1") (pinfunction "1_1") (pintype "passive"))
      (node (ref "J35") (pin "2") (pinfunction "2_2") (pintype "passive"))
      (node (ref "J35") (pin "3") (pinfunction "3_3") (pintype "passive"))
      (node (ref "J35") (pin "4") (pinfunction "4_4") (pintype "passive"))
      (node (ref "J35") (pin "5") (pinfunction "5_5") (pintype "passive"))
    )
    (net (code "29") (name "Net-(J36-Pad1)") (class "Default")
      (node (ref "J36") (pin "1") (pinfunction "1_1") (pintype "passive"))
      (node (ref "J36") (pin "2") (pinfunction "2_2") (pintype "passive"))
      (node (ref "J36") (pin "3") (pinfunction "3_3") (pintype "passive"))
      (node (ref "J36") (pin "4") (pinfunction "4_4") (pintype "passive"))
      (node (ref "J36") (pin "5") (pinfunction "5_5") (pintype "passive"))
    )
    (net (code "30") (name "Net-(J37-Pad1)") (class "Default")
      (node (ref "J37") (pin "1") (pinfunction "1_1") (pintype "passive"))
      (node (ref "J37") (pin "2") (pinfunction "2_2") (pintype "passive"))
      (node (ref "J37") (pin "3") (pinfunction "3_3") (pintype "passive"))
      (node (ref "J37") (pin "4") (pinfunction "4_4") (pintype "passive"))
      (node (ref "J37") (pin "5") (pinfunction "5_5") (pintype "passive"))
    )
    (net (code "31") (name "Net-(J38-Pad1)") (class "Default")
      (node (ref "J38") (pin "1") (pinfunction "1_1") (pintype "passive"))
      (node (ref "J38") (pin "2") (pinfunction "2_2") (pintype "passive"))
      (node (ref "J38") (pin "3") (pinfunction "3_3") (pintype "passive"))
      (node (ref "J38") (pin "4") (pinfunction "4_4") (pintype "passive"))
      (node (ref "J38") (pin "5") (pinfunction "5_5") (pintype "passive"))
    )
    (net (code "32") (name "Net-(J39-Pad1)") (class "Default")
      (node (ref "J39") (pin "1") (pinfunction "1_1") (pintype "passive"))
      (node (ref "J39") (pin "2") (pinfunction "2_2") (pintype "passive"))
      (node (ref "J39") (pin "3") (pinfunction "3_3") (pintype "passive"))
      (node (ref "J39") (pin "4") (pinfunction "4_4") (pintype "passive"))
      (node (ref "J39") (pin "5") (pinfunction "5_5") (pintype "passive"))
    )
    (net (code "33") (name "Net-(J40-Pad1)") (class "Default")
      (node (ref "J40") (pin "1") (pinfunction "1_1") (pintype "passive"))
      (node (ref "J40") (pin "2") (pinfunction "2_2") (pintype "passive"))
      (node (ref "J40") (pin "3") (pinfunction "3_3") (pintype "passive"))
      (node (ref "J40") (pin "4") (pinfunction "4_4") (pintype "passive"))
      (node (ref "J40") (pin "5") (pinfunction "5_5") (pintype "passive"))
    )
    (net (code "34") (name "Net-(J41-Pad1)") (class "Default")
      (node (ref "J41") (pin "1") (pinfunction "1_1") (pintype "passive"))
      (node (ref "J41") (pin "2") (pinfunction "2_2") (pintype "passive"))
      (node (ref "J41") (pin "3") (pinfunction "3_3") (pintype "passive"))
      (node (ref "J41") (pin "4") (pinfunction "4_4") (pintype "passive"))
      (node (ref "J41") (pin "5") (pinfunction "5_5") (pintype "passive"))
    )
    (net (code "35") (name "Net-(J42-Pad1)") (class "Default")
      (node (ref "J42") (pin "1") (pinfunction "1_1") (pintype "passive"))
      (node (ref "J42") (pin "2") (pinfunction "2_2") (pintype "passive"))
      (node (ref "J42") (pin "3") (pinfunction "3_3") (pintype "passive"))
      (node (ref "J42") (pin "4") (pinfunction "4_4") (pintype "passive"))
      (node (ref "J42") (pin "5") (pinfunction "5_5") (pintype "passive"))
    )
    (net (code "36") (name "Net-(J43-Pad1)") (class "Default")
      (node (ref "J43") (pin "1") (pinfunction "1_1") (pintype "passive"))
      (node (ref "J43") (pin "2") (pinfunction "2_2") (pintype "passive"))
      (node (ref "J43") (pin "3") (pinfunction "3_3") (pintype "passive"))
      (node (ref "J43") (pin "4") (pinfunction "4_4") (pintype "passive"))
      (node (ref "J43") (pin "5") (pinfunction "5_5") (pintype "passive"))
    )
    (net (code "37") (name "Net-(J44-Pad1)") (class "Default")
      (node (ref "J44") (pin "1") (pinfunction "1_1") (pintype "passive"))
      (node (ref "J44") (pin "2") (pinfunction "2_2") (pintype "passive"))
      (node (ref "J44") (pin "3") (pinfunction "3_3") (pintype "passive"))
      (node (ref "J44") (pin "4") (pinfunction "4_4") (pintype "passive"))
      (node (ref "J44") (pin "5") (pinfunction "5_5") (pintype "passive"))
    )
    (net (code "38") (name "Net-(J83-Pad2)") (class "Default")
      (node (ref "J83") (pin "2") (pinfunction "2_2") (pintype "passive"))
      (node (ref "R11") (pin "1") (pinfunction "1_1") (pintype "passive"))
      (node (ref "R12") (pin "2") (pinfunction "2_2") (pintype "passive"))
    )
    (net (code "39") (name "Net-(J84-Pad2)") (class "Default")
      (node (ref "J84") (pin "2") (pinfunction "2_2") (pintype "passive"))
      (node (ref "R13") (pin "1") (pinfunction "1_1") (pintype "passive"))
      (node (ref "R14") (pin "2") (pinfunction "2_2") (pintype "passive"))
    )
    (net (code "40") (name "Net-(J89-Pad1)") (class "Default")
      (node (ref "J89") (pin "1") (pinfunction "1_1") (pintype "passive"))
      (node (ref "J89") (pin "10") (pinfunction "10_10") (pintype "passive"))
      (node (ref "J89") (pin "11") (pinfunction "11_11") (pintype "passive"))
      (node (ref "J89") (pin "12") (pinfunction "12_12") (pintype "passive"))
      (node (ref "J89") (pin "13") (pinfunction "13_13") (pintype "passive"))
      (node (ref "J89") (pin "14") (pinfunction "14_14") (pintype "passive"))
      (node (ref "J89") (pin "15") (pinfunction "15_15") (pintype "passive"))
      (node (ref "J89") (pin "16") (pinfunction "16_16") (pintype "passive"))
      (node (ref "J89") (pin "17") (pinfunction "17_17") (pintype "passive"))
      (node (ref "J89") (pin "18") (pinfunction "18_18") (pintype "passive"))
      (node (ref "J89") (pin "19") (pinfunction "19_19") (pintype "passive"))
      (node (ref "J89") (pin "2") (pinfunction "2_2") (pintype "passive"))
      (node (ref "J89") (pin "20") (pinfunction "20_20") (pintype "passive"))
      (node (ref "J89") (pin "21") (pinfunction "21_21") (pintype "passive"))
      (node (ref "J89") (pin "22") (pinfunction "22_22") (pintype "passive"))
      (node (ref "J89") (pin "23") (pinfunction "23_23") (pintype "passive"))
      (node (ref "J89") (pin "24") (pinfunction "24_24") (pintype "passive"))
      (node (ref "J89") (pin "25") (pinfunction "25_25") (pintype "passive"))
      (node (ref "J89") (pin "26") (pinfunction "26_26") (pintype "passive"))
      (node (ref "J89") (pin "27") (pinfunction "27_27") (pintype "passive"))
      (node (ref "J89") (pin "28") (pinfunction "28_28") (pintype "passive"))
      (node (ref "J89") (pin "29") (pinfunction "29_29") (pintype "passive"))
      (node (ref "J89") (pin "3") (pinfunction "3_3") (pintype "passive"))
      (node (ref "J89") (pin "30") (pinfunction "30_30") (pintype "passive"))
      (node (ref "J89") (pin "4") (pinfunction "4_4") (pintype "passive"))
      (node (ref "J89") (pin "5") (pinfunction "5_5") (pintype "passive"))
      (node (ref "J89") (pin "6") (pinfunction "6_6") (pintype "passive"))
      (node (ref "J89") (pin "7") (pinfunction "7_7") (pintype "passive"))
      (node (ref "J89") (pin "8") (pinfunction "8_8") (pintype "passive"))
      (node (ref "J89") (pin "9") (pinfunction "9_9") (pintype "passive"))
    )
    (net (code "41") (name "Net-(J90-Pad1)") (class "Default")
      (node (ref "J90") (pin "1") (pinfunction "1_1") (pintype "passive"))
      (node (ref "J90") (pin "10") (pinfunction "10_10") (pintype "passive"))
      (node (ref "J90") (pin "11") (pinfunction "11_11") (pintype "passive"))
      (node (ref "J90") (pin "12") (pinfunction "12_12") (pintype "passive"))
      (node (ref "J90") (pin "13") (pinfunction "13_13") (pintype "passive"))
      (node (ref "J90") (pin "14") (pinfunction "14_14") (pintype "passive"))
      (node (ref "J90") (pin "15") (pinfunction "15_15") (pintype "passive"))
      (node (ref "J90") (pin "16") (pinfunction "16_16") (pintype "passive"))
      (node (ref "J90") (pin "17") (pinfunction "17_17") (pintype "passive"))
      (node (ref "J90") (pin "18") (pinfunction "18_18") (pintype "passive"))
      (node (ref "J90") (pin "19") (pinfunction "19_19") (pintype "passive"))
      (node (ref "J90") (pin "2") (pinfunction "2_2") (pintype "passive"))
      (node (ref "J90") (pin "20") (pinfunction "20_20") (pintype "passive"))
      (node (ref "J90") (pin "21") (pinfunction "21_21") (pintype "passive"))
      (node (ref "J90") (pin "22") (pinfunction "22_22") (pintype "passive"))
      (node (ref "J90") (pin "23") (pinfunction "23_23") (pintype "passive"))
      (node (ref "J90") (pin "24") (pinfunction "24_24") (pintype "passive"))
      (node (ref "J90") (pin "25") (pinfunction "25_25") (pintype "passive"))
      (node (ref "J90") (pin "26") (pinfunction "26_26") (pintype "passive"))
      (node (ref "J90") (pin "27") (pinfunction "27_27") (pintype "passive"))
      (node (ref "J90") (pin "28") (pinfunction "28_28") (pintype "passive"))
      (node (ref "J90") (pin "29") (pinfunction "29_29") (pintype "passive"))
      (node (ref "J90") (pin "3") (pinfunction "3_3") (pintype "passive"))
      (node (ref "J90") (pin "30") (pinfunction "30_30") (pintype "passive"))
      (node (ref "J90") (pin "4") (pinfunction "4_4") (pintype "passive"))
      (node (ref "J90") (pin "5") (pinfunction "5_5") (pintype "passive"))
      (node (ref "J90") (pin "6") (pinfunction "6_6") (pintype "passive"))
      (node (ref "J90") (pin "7") (pinfunction "7_7") (pintype "passive"))
      (node (ref "J90") (pin "8") (pinfunction "8_8") (pintype "passive"))
      (node (ref "J90") (pin "9") (pinfunction "9_9") (pintype "passive"))
    )
    (net (code "42") (name "Net-(J91-Pad1)") (class "Default")
      (node (ref "J91") (pin "1") (pinfunction "1_1") (pintype "passive"))
      (node (ref "J91") (pin "2") (pinfunction "2_2") (pintype "passive"))
      (node (ref "J91") (pin "3") (pinfunction "3_3") (pintype "passive"))
      (node (ref "J91") (pin "4") (pinfunction "4_4") (pintype "passive"))
    )
    (net (code "43") (name "Net-(J92-Pad1)") (class "Default")
      (node (ref "J92") (pin "1") (pinfunction "1_1") (pintype "passive"))
      (node (ref "J92") (pin "2") (pinfunction "2_2") (pintype "passive"))
      (node (ref "J92") (pin "3") (pinfunction "3_3") (pintype "passive"))
      (node (ref "J92") (pin "4") (pinfunction "4_4") (pintype "passive"))
    )
    (net (code "44") (name "Net-(J93-Pad1)") (class "Default")
      (node (ref "J93") (pin "1") (pinfunction "1_1") (pintype "passive"))
      (node (ref "J93") (pin "2") (pinfunction "2_2") (pintype "passive"))
      (node (ref "J93") (pin "3") (pinfunction "3_3") (pintype "passive"))
      (node (ref "J93") (pin "4") (pinfunction "4_4") (pintype "passive"))
    )
    (net (code "45") (name "Net-(J94-Pad1)") (class "Default")
      (node (ref "J94") (pin "1") (pinfunction "1_1") (pintype "passive"))
      (node (ref "J94") (pin "10") (pinfunction "10_10") (pintype "passive"))
      (node (ref "J94") (pin "11") (pinfunction "11_11") (pintype "passive"))
      (node (ref "J94") (pin "12") (pinfunction "12_12") (pintype "passive"))
      (node (ref "J94") (pin "13") (pinfunction "13_13") (pintype "passive"))
      (node (ref "J94") (pin "14") (pinfunction "14_14") (pintype "passive"))
      (node (ref "J94") (pin "15") (pinfunction "15_15") (pintype "passive"))
      (node (ref "J94") (pin "16") (pinfunction "16_16") (pintype "passive"))
      (node (ref "J94") (pin "17") (pinfunction "17_17") (pintype "passive"))
      (node (ref "J94") (pin "18") (pinfunction "18_18") (pintype "passive"))
      (node (ref "J94") (pin "19") (pinfunction "19_19") (pintype "passive"))
      (node (ref "J94") (pin "2") (pinfunction "2_2") (pintype "passive"))
      (node (ref "J94") (pin "20") (pinfunction "20_20") (pintype "passive"))
      (node (ref "J94") (pin "21") (pinfunction "21_21") (pintype "passive"))
      (node (ref "J94") (pin "22") (pinfunction "22_22") (pintype "passive"))
      (node (ref "J94") (pin "23") (pinfunction "23_23") (pintype "passive"))
      (node (ref "J94") (pin "24") (pinfunction "24_24") (pintype "passive"))
      (node (ref "J94") (pin "25") (pinfunction "25_25") (pintype "passive"))
      (node (ref "J94") (pin "26") (pinfunction "26_26") (pintype "passive"))
      (node (ref "J94") (pin "27") (pinfunction "27_27") (pintype "passive"))
      (node (ref "J94") (pin "28") (pinfunction "28_28") (pintype "passive"))
      (node (ref "J94") (pin "29") (pinfunction "29_29") (pintype "passive"))
      (node (ref "J94") (pin "3") (pinfunction "3_3") (pintype "passive"))
      (node (ref "J94") (pin "30") (pinfunction "30_30") (pintype "passive"))
      (node (ref "J94") (pin "4") (pinfunction "4_4") (pintype "passive"))
      (node (ref "J94") (pin "5") (pinfunction "5_5") (pintype "passive"))
      (node (ref "J94") (pin "6") (pinfunction "6_6") (pintype "passive"))
      (node (ref "J94") (pin "7") (pinfunction "7_7") (pintype "passive"))
      (node (ref "J94") (pin "8") (pinfunction "8_8") (pintype "passive"))
      (node (ref "J94") (pin "9") (pinfunction "9_9") (pintype "passive"))
    )
    (net (code "46") (name "Net-(J95-Pad1)") (class "Default")
      (node (ref "J95") (pin "1") (pinfunction "1_1") (pintype "passive"))
      (node (ref "J95") (pin "10") (pinfunction "10_10") (pintype "passive"))
      (node (ref "J95") (pin "11") (pinfunction "11_11") (pintype "passive"))
      (node (ref "J95") (pin "12") (pinfunction "12_12") (pintype "passive"))
      (node (ref "J95") (pin "13") (pinfunction "13_13") (pintype "passive"))
      (node (ref "J95") (pin "14") (pinfunction "14_14") (pintype "passive"))
      (node (ref "J95") (pin "15") (pinfunction "15_15") (pintype "passive"))
      (node (ref "J95") (pin "16") (pinfunction "16_16") (pintype "passive"))
      (node (ref "J95") (pin "17") (pinfunction "17_17") (pintype "passive"))
      (node (ref "J95") (pin "18") (pinfunction "18_18") (pintype "passive"))
      (node (ref "J95") (pin "19") (pinfunction "19_19") (pintype "passive"))
      (node (ref "J95") (pin "2") (pinfunction "2_2") (pintype "passive"))
      (node (ref "J95") (pin "20") (pinfunction "20_20") (pintype "passive"))
      (node (ref "J95") (pin "21") (pinfunction "21_21") (pintype "passive"))
      (node (ref "J95") (pin "22") (pinfunction "22_22") (pintype "passive"))
      (node (ref "J95") (pin "23") (pinfunction "23_23") (pintype "passive"))
      (node (ref "J95") (pin "24") (pinfunction "24_24") (pintype "passive"))
      (node (ref "J95") (pin "25") (pinfunction "25_25") (pintype "passive"))
      (node (ref "J95") (pin "26") (pinfunction "26_26") (pintype "passive"))
      (node (ref "J95") (pin "27") (pinfunction "27_27") (pintype "passive"))
      (node (ref "J95") (pin "28") (pinfunction "28_28") (pintype "passive"))
      (node (ref "J95") (pin "29") (pinfunction "29_29") (pintype "passive"))
      (node (ref "J95") (pin "3") (pinfunction "3_3") (pintype "passive"))
      (node (ref "J95") (pin "30") (pinfunction "30_30") (pintype "passive"))
      (node (ref "J95") (pin "4") (pinfunction "4_4") (pintype "passive"))
      (node (ref "J95") (pin "5") (pinfunction "5_5") (pintype "passive"))
      (node (ref "J95") (pin "6") (pinfunction "6_6") (pintype "passive"))
      (node (ref "J95") (pin "7") (pinfunction "7_7") (pintype "passive"))
      (node (ref "J95") (pin "8") (pinfunction "8_8") (pintype "passive"))
      (node (ref "J95") (pin "9") (pinfunction "9_9") (pintype "passive"))
    )
    (net (code "47") (name "Net-(J96-Pad1)") (class "Default")
      (node (ref "J96") (pin "1") (pinfunction "1_1") (pintype "passive"))
      (node (ref "J96") (pin "2") (pinfunction "2_2") (pintype "passive"))
      (node (ref "J96") (pin "3") (pinfunction "3_3") (pintype "passive"))
      (node (ref "J96") (pin "4") (pinfunction "4_4") (pintype "passive"))
    )
    (net (code "48") (name "Net-(LED3-PadA)") (class "Default")
      (node (ref "LED3") (pin "A") (pinfunction "A_A") (pintype "passive"))
      (node (ref "R15") (pin "1") (pinfunction "1_1") (pintype "passive"))
    )
    (net (code "49") (name "Net-(LED4-PadA)") (class "Default")
      (node (ref "LED4") (pin "A") (pinfunction "A_A") (pintype "passive"))
      (node (ref "R16") (pin "1") (pinfunction "1_1") (pintype "passive"))
    )
    (net (code "50") (name "Net-(U4-IN)") (class "Default")
      (node (ref "C12") (pin "1") (pinfunction "1_1") (pintype "passive"))
      (node (ref "D3") (pin "C") (pinfunction "C_C") (pintype "passive"))
      (node (ref "D4") (pin "C") (pinfunction "C_C") (pintype "passive"))
      (node (ref "U4") (pin "3") (pinfunction "IN_3") (pintype "bidirectional"))
    )
    (net (code "51") (name "OSC32_IN") (class "Default")
      (node (ref "Q4") (pin "3") (pinfunction "OUT_3") (pintype "output"))
      (node (ref "U3") (pin "3") (pinfunction "PC14-OSC32_IN_3") (pintype "bidirectional"))
    )
    (net (code "52") (name "OSC32_OUT") (class "Default")
      (node (ref "U3") (pin "4") (pinfunction "PC15-OSC32_OUT_4") (pintype "bidirectional"))
    )
    (net (code "53") (name "OSC_IN") (class "Default")
      (node (ref "Q3") (pin "3") (pinfunction "OUT_3") (pintype "output"))
      (node (ref "U3") (pin "5") (pinfunction "OSC_IN_5") (pintype "input"))
    )
    (net (code "54") (name "OSC_OUT") (class "Default")
      (node (ref "U3") (pin "6") (pinfunction "OSC_OUT_6") (pintype "output"))
    )
    (net (code "55") (name "PA0") (class "Default")
      (node (ref "J72") (pin "1") (pinfunction "1_1") (pintype "passive"))
      (node (ref "J72") (pin "2") (pinfunction "2_2") (pintype "passive"))
      (node (ref "J86") (pin "5") (pinfunction "5_5") (pintype "passive"))
      (node (ref "U3") (pin "10") (pinfunction "PA0-WKUP_10") (pintype "bidirectional"))
    )
    (net (code "56") (name "PA1") (class "Default")
      (node (ref "J74") (pin "1") (pinfunction "1_1") (pintype "passive"))
      (node (ref "J74") (pin "2") (pinfunction "2_2") (pintype "passive"))
      (node (ref "J86") (pin "4") (pinfunction "4_4") (pintype "passive"))
      (node (ref "U3") (pin "11") (pinfunction "PA1_11") (pintype "bidirectional"))
    )
    (net (code "57") (name "PA2") (class "Default")
      (node (ref "J76") (pin "1") (pinfunction "1_1") (pintype "passive"))
      (node (ref "J76") (pin "2") (pinfunction "2_2") (pintype "passive"))
      (node (ref "J86") (pin "3") (pinfunction "3_3") (pintype "passive"))
      (node (ref "U3") (pin "12") (pinfunction "PA2_12") (pintype "bidirectional"))
    )
    (net (code "58") (name "PA3") (class "Default")
      (node (ref "J80") (pin "1") (pinfunction "1_1") (pintype "passive"))
      (node (ref "J80") (pin "2") (pinfunction "2_2") (pintype "passive"))
      (node (ref "J85") (pin "1") (pinfunction "1_1") (pintype "passive"))
      (node (ref "J85") (pin "2") (pinfunction "2_2") (pintype "passive"))
      (node (ref "J86") (pin "1") (pinfunction "1_1") (pintype "passive"))
      (node (ref "R16") (pin "2") (pinfunction "2_2") (pintype "passive"))
      (node (ref "U3") (pin "13") (pinfunction "PA3_13") (pintype "bidirectional"))
    )
    (net (code "59") (name "PA4") (class "Default")
      (node (ref "J79") (pin "1") (pinfunction "1_1") (pintype "passive"))
      (node (ref "J79") (pin "2") (pinfunction "2_2") (pintype "passive"))
      (node (ref "J87") (pin "1") (pinfunction "1_1") (pintype "passive"))
      (node (ref "U3") (pin "14") (pinfunction "PA4_14") (pintype "bidirectional"))
    )
    (net (code "60") (name "PA5") (class "Default")
      (node (ref "J77") (pin "1") (pinfunction "1_1") (pintype "passive"))
      (node (ref "J77") (pin "2") (pinfunction "2_2") (pintype "passive"))
      (node (ref "J87") (pin "2") (pinfunction "2_2") (pintype "passive"))
      (node (ref "U3") (pin "15") (pinfunction "PA5_15") (pintype "bidirectional"))
    )
    (net (code "61") (name "PA6") (class "Default")
      (node (ref "J75") (pin "1") (pinfunction "1_1") (pintype "passive"))
      (node (ref "J75") (pin "2") (pinfunction "2_2") (pintype "passive"))
      (node (ref "J87") (pin "3") (pinfunction "3_3") (pintype "passive"))
      (node (ref "U3") (pin "16") (pinfunction "PA6_16") (pintype "bidirectional"))
    )
    (net (code "62") (name "PA7") (class "Default")
      (node (ref "J73") (pin "1") (pinfunction "1_1") (pintype "passive"))
      (node (ref "J73") (pin "2") (pinfunction "2_2") (pintype "passive"))
      (node (ref "J87") (pin "4") (pinfunction "4_4") (pintype "passive"))
      (node (ref "U3") (pin "17") (pinfunction "PA7_17") (pintype "bidirectional"))
    )
    (net (code "63") (name "PA8*") (class "Default")
      (node (ref "J53") (pin "1") (pinfunction "1_1") (pintype "passive"))
      (node (ref "J53") (pin "2") (pinfunction "2_2") (pintype "passive"))
      (node (ref "J88") (pin "3") (pinfunction "3_3") (pintype "passive"))
      (node (ref "U3") (pin "29") (pinfunction "PA8_29") (pintype "bidirectional"))
    )
    (net (code "64") (name "PA9*") (class "Default")
      (node (ref "J51") (pin "1") (pinfunction "1_1") (pintype "passive"))
      (node (ref "J51") (pin "2") (pinfunction "2_2") (pintype "passive"))
      (node (ref "J88") (pin "4") (pinfunction "4_4") (pintype "passive"))
      (node (ref "U3") (pin "30") (pinfunction "PA9_30") (pintype "bidirectional"))
    )
    (net (code "65") (name "PA10*") (class "Default")
      (node (ref "J49") (pin "1") (pinfunction "1_1") (pintype "passive"))
      (node (ref "J49") (pin "2") (pinfunction "2_2") (pintype "passive"))
      (node (ref "J88") (pin "5") (pinfunction "5_5") (pintype "passive"))
      (node (ref "U3") (pin "31") (pinfunction "PA10_31") (pintype "bidirectional"))
    )
    (net (code "66") (name "PB0") (class "Default")
      (node (ref "J71") (pin "1") (pinfunction "1_1") (pintype "passive"))
      (node (ref "J71") (pin "2") (pinfunction "2_2") (pintype "passive"))
      (node (ref "J87") (pin "5") (pinfunction "5_5") (pintype "passive"))
      (node (ref "U3") (pin "18") (pinfunction "PB0_18") (pintype "bidirectional"))
    )
    (net (code "67") (name "PB1") (class "Default")
      (node (ref "J69") (pin "1") (pinfunction "1_1") (pintype "passive"))
      (node (ref "J69") (pin "2") (pinfunction "2_2") (pintype "passive"))
      (node (ref "J87") (pin "6") (pinfunction "6_6") (pintype "passive"))
      (node (ref "U3") (pin "19") (pinfunction "PB1_19") (pintype "bidirectional"))
    )
    (net (code "68") (name "PB5") (class "Default")
      (node (ref "J58") (pin "1") (pinfunction "1_1") (pintype "passive"))
      (node (ref "J58") (pin "2") (pinfunction "2_2") (pintype "passive"))
      (node (ref "J86") (pin "12") (pinfunction "12_12") (pintype "passive"))
      (node (ref "U3") (pin "41") (pinfunction "PB5_41") (pintype "bidirectional"))
    )
    (net (code "69") (name "PB6*") (class "Default")
      (node (ref "J60") (pin "1") (pinfunction "1_1") (pintype "passive"))
      (node (ref "J60") (pin "2") (pinfunction "2_2") (pintype "passive"))
      (node (ref "J86") (pin "11") (pinfunction "11_11") (pintype "passive"))
      (node (ref "U3") (pin "42") (pinfunction "PB6_42") (pintype "bidirectional"))
    )
    (net (code "70") (name "PB7*") (class "Default")
      (node (ref "J62") (pin "1") (pinfunction "1_1") (pintype "passive"))
      (node (ref "J62") (pin "2") (pinfunction "2_2") (pintype "passive"))
      (node (ref "J86") (pin "10") (pinfunction "10_10") (pintype "passive"))
      (node (ref "U3") (pin "43") (pinfunction "PB7_43") (pintype "bidirectional"))
    )
    (net (code "71") (name "PB8*") (class "Default")
      (node (ref "J64") (pin "1") (pinfunction "1_1") (pintype "passive"))
      (node (ref "J64") (pin "2") (pinfunction "2_2") (pintype "passive"))
      (node (ref "J86") (pin "9") (pinfunction "9_9") (pintype "passive"))
      (node (ref "U3") (pin "45") (pinfunction "PB8_45") (pintype "bidirectional"))
    )
    (net (code "72") (name "PB9*") (class "Default")
      (node (ref "J66") (pin "1") (pinfunction "1_1") (pintype "passive"))
      (node (ref "J66") (pin "2") (pinfunction "2_2") (pintype "passive"))
      (node (ref "J86") (pin "8") (pinfunction "8_8") (pintype "passive"))
      (node (ref "U3") (pin "46") (pinfunction "PB9_46") (pintype "bidirectional"))
    )
    (net (code "73") (name "PB10*") (class "Default")
      (node (ref "J65") (pin "1") (pinfunction "1_1") (pintype "passive"))
      (node (ref "J65") (pin "2") (pinfunction "2_2") (pintype "passive"))
      (node (ref "J87") (pin "8") (pinfunction "8_8") (pintype "passive"))
      (node (ref "U3") (pin "21") (pinfunction "PB10_21") (pintype "bidirectional"))
    )
    (net (code "74") (name "PB11*") (class "Default")
      (node (ref "J63") (pin "1") (pinfunction "1_1") (pintype "passive"))
      (node (ref "J63") (pin "2") (pinfunction "2_2") (pintype "passive"))
      (node (ref "J87") (pin "9") (pinfunction "9_9") (pintype "passive"))
      (node (ref "U3") (pin "22") (pinfunction "PB11_22") (pintype "bidirectional"))
    )
    (net (code "75") (name "PB12*") (class "Default")
      (node (ref "J61") (pin "1") (pinfunction "1_1") (pintype "passive"))
      (node (ref "J61") (pin "2") (pinfunction "2_2") (pintype "passive"))
      (node (ref "J87") (pin "10") (pinfunction "10_10") (pintype "passive"))
      (node (ref "U3") (pin "25") (pinfunction "PB12_25") (pintype "bidirectional"))
    )
    (net (code "76") (name "PB13*") (class "Default")
      (node (ref "J59") (pin "1") (pinfunction "1_1") (pintype "passive"))
      (node (ref "J59") (pin "2") (pinfunction "2_2") (pintype "passive"))
      (node (ref "J87") (pin "11") (pinfunction "11_11") (pintype "passive"))
      (node (ref "U3") (pin "26") (pinfunction "PB13_26") (pintype "bidirectional"))
    )
    (net (code "77") (name "PB14*") (class "Default")
      (node (ref "J57") (pin "1") (pinfunction "1_1") (pintype "passive"))
      (node (ref "J57") (pin "2") (pinfunction "2_2") (pintype "passive"))
      (node (ref "J88") (pin "1") (pinfunction "1_1") (pintype "passive"))
      (node (ref "U3") (pin "27") (pinfunction "PB14_27") (pintype "bidirectional"))
    )
    (net (code "78") (name "PB15*") (class "Default")
      (node (ref "J55") (pin "1") (pinfunction "1_1") (pintype "passive"))
      (node (ref "J55") (pin "2") (pinfunction "2_2") (pintype "passive"))
      (node (ref "J88") (pin "2") (pinfunction "2_2") (pintype "passive"))
      (node (ref "U3") (pin "28") (pinfunction "PB15_28") (pintype "bidirectional"))
    )
    (net (code "79") (name "PC13") (class "Default")
      (node (ref "J70") (pin "1") (pinfunction "1_1") (pintype "passive"))
      (node (ref "J70") (pin "2") (pinfunction "2_2") (pintype "passive"))
      (node (ref "J86") (pin "6") (pinfunction "6_6") (pintype "passive"))
      (node (ref "U3") (pin "2") (pinfunction "PC13_2") (pintype "bidirectional"))
    )
    (net (code "80") (name "SWCLK*") (class "Default")
      (node (ref "J20") (pin "1") (pinfunction "1_1") (pintype "passive"))
      (node (ref "J20") (pin "2") (pinfunction "2_2") (pintype "passive"))
      (node (ref "J82") (pin "4") (pinfunction "SWDCLK/TCK_4") (pintype "bidirectional"))
      (node (ref "J86") (pin "19") (pinfunction "19_19") (pintype "passive"))
      (node (ref "J98") (pin "2") (pinfunction "2_2") (pintype "bidirectional"))
      (node (ref "U3") (pin "37") (pinfunction "PA14_37") (pintype "bidirectional"))
    )
    (net (code "81") (name "SWDIO*") (class "Default")
      (node (ref "J48") (pin "1") (pinfunction "1_1") (pintype "passive"))
      (node (ref "J48") (pin "2") (pinfunction "2_2") (pintype "passive"))
      (node (ref "J82") (pin "2") (pinfunction "SWDIO/TMS_2") (pintype "bidirectional"))
      (node (ref "J86") (pin "17") (pinfunction "17_17") (pintype "passive"))
      (node (ref "J98") (pin "1") (pinfunction "1_1") (pintype "bidirectional"))
      (node (ref "U3") (pin "34") (pinfunction "PA13_34") (pintype "bidirectional"))
    )
    (net (code "82") (name "SWO*") (class "Default")
      (node (ref "J50") (pin "1") (pinfunction "1_1") (pintype "passive"))
      (node (ref "J50") (pin "2") (pinfunction "2_2") (pintype "passive"))
      (node (ref "J82") (pin "6") (pinfunction "SWO/TDO_6") (pintype "bidirectional"))
      (node (ref "J86") (pin "16") (pinfunction "16_16") (pintype "passive"))
      (node (ref "J98") (pin "3") (pinfunction "3_3") (pintype "bidirectional"))
      (node (ref "U3") (pin "39") (pinfunction "PB3_39") (pintype "bidirectional"))
    )
    (net (code "83") (name "USB_DM*") (class "Default")
      (node (ref "J19") (pin "1") (pinfunction "1_1") (pintype "passive"))
      (node (ref "J19") (pin "2") (pinfunction "2_2") (pintype "passive"))
      (node (ref "J88") (pin "8") (pinfunction "8_8") (pintype "passive"))
      (node (ref "J97") (pin "2") (pinfunction "2_2") (pintype "bidirectional"))
      (node (ref "U3") (pin "32") (pinfunction "PA11_32") (pintype "bidirectional"))
    )
    (net (code "84") (name "USB_DP*") (class "Default")
      (node (ref "J17") (pin "1") (pinfunction "1_1") (pintype "passive"))
      (node (ref "J17") (pin "2") (pinfunction "2_2") (pintype "passive"))
      (node (ref "J88") (pin "9") (pinfunction "9_9") (pintype "passive"))
      (node (ref "J97") (pin "3") (pinfunction "3_3") (pintype "bidirectional"))
      (node (ref "R9") (pin "1") (pinfunction "1_1") (pintype "passive"))
      (node (ref "U3") (pin "33") (pinfunction "PA12_33") (pintype "bidirectional"))
    )
    (net (code "85") (name "VBAT_1.8-3.6V") (class "Default")
      (node (ref "C19") (pin "1") (pinfunction "1_1") (pintype "passive"))
      (node (ref "J68") (pin "1") (pinfunction "1_1") (pintype "passive"))
      (node (ref "J68") (pin "2") (pinfunction "2_2") (pintype "passive"))
      (node (ref "J86") (pin "7") (pinfunction "7_7") (pintype "passive"))
      (node (ref "R10") (pin "1") (pinfunction "1_1") (pintype "passive"))
      (node (ref "U3") (pin "1") (pinfunction "VBAT_1") (pintype "power_in"))
    )
    (net (code "86") (name "VDD") (class "Default")
      (node (ref "C13") (pin "1") (pinfunction "1_1") (pintype "passive"))
      (node (ref "C14") (pin "1") (pinfunction "1_1") (pintype "passive"))
      (node (ref "C15") (pin "1") (pinfunction "1_1") (pintype "passive"))
      (node (ref "C16") (pin "1") (pinfunction "1_1") (pintype "passive"))
      (node (ref "C21") (pin "1") (pinfunction "1_1") (pintype "passive"))
      (node (ref "C22") (pin "1") (pinfunction "1_1") (pintype "passive"))
      (node (ref "J18") (pin "1") (pinfunction "1_1") (pintype "passive"))
      (node (ref "J18") (pin "2") (pinfunction "2_2") (pintype "passive"))
      (node (ref "J82") (pin "1") (pinfunction "VCC_1") (pintype "bidirectional"))
      (node (ref "J83") (pin "3") (pinfunction "3_3") (pintype "passive"))
      (node (ref "J84") (pin "3") (pinfunction "3_3") (pintype "passive"))
      (node (ref "J86") (pin "20") (pinfunction "20_20") (pintype "passive"))
      (node (ref "J98") (pin "4") (pinfunction "4_4") (pintype "bidirectional"))
      (node (ref "L2") (pin "2") (pinfunction "2_2") (pintype "passive"))
      (node (ref "Q3") (pin "4") (pinfunction "VDD_4") (pintype "power_in"))
      (node (ref "Q4") (pin "4") (pinfunction "VDD_4") (pintype "power_in"))
      (node (ref "R10") (pin "2") (pinfunction "2_2") (pintype "passive"))
      (node (ref "R15") (pin "2") (pinfunction "2_2") (pintype "passive"))
      (node (ref "R9") (pin "2") (pinfunction "2_2") (pintype "passive"))
      (node (ref "U3") (pin "24") (pinfunction "VDD_1_24") (pintype "power_in"))
      (node (ref "U3") (pin "36") (pinfunction "VDD_2_36") (pintype "power_in"))
      (node (ref "U3") (pin "48") (pinfunction "VDD_3_48") (pintype "power_in"))
      (node (ref "U4") (pin "2") (pinfunction "OUT_2") (pintype "bidirectional"))
      (node (ref "U4") (pin "TER") (pinfunction "OUT_TER") (pintype "bidirectional"))
    )
    (net (code "87") (name "VIN_4.8-15V") (class "Default")
      (node (ref "D4") (pin "A") (pinfunction "A_A") (pintype "passive"))
      (node (ref "J47") (pin "1") (pinfunction "1_1") (pintype "passive"))
      (node (ref "J47") (pin "2") (pinfunction "2_2") (pintype "passive"))
      (node (ref "J88") (pin "6") (pinfunction "6_6") (pintype "passive"))
    )
    (net (code "88") (name "VUSB") (class "Default")
      (node (ref "D3") (pin "A") (pinfunction "A_A") (pintype "passive"))
      (node (ref "J45") (pin "1") (pinfunction "1_1") (pintype "passive"))
      (node (ref "J45") (pin "2") (pinfunction "2_2") (pintype "passive"))
      (node (ref "J88") (pin "7") (pinfunction "7_7") (pintype "passive"))
      (node (ref "J97") (pin "1") (pinfunction "1_1") (pintype "bidirectional"))
    )
    (net (code "89") (name "unconnected-(J82-KEY-Pad7)") (class "Default")
      (node (ref "J82") (pin "7") (pinfunction "KEY_7") (pintype "bidirectional"))
    )
    (net (code "90") (name "unconnected-(Q3-VC-Pad1)") (class "Default")
      (node (ref "Q3") (pin "1") (pinfunction "VC_1") (pintype "input"))
    )
    (net (code "91") (name "unconnected-(Q4-VC-Pad1)") (class "Default")
      (node (ref "Q4") (pin "1") (pinfunction "VC_1") (pintype "input"))
    )
  )
)
